# PowerBoard_p1.net
KiCad netlist of a schematic drawn in Altium Designer
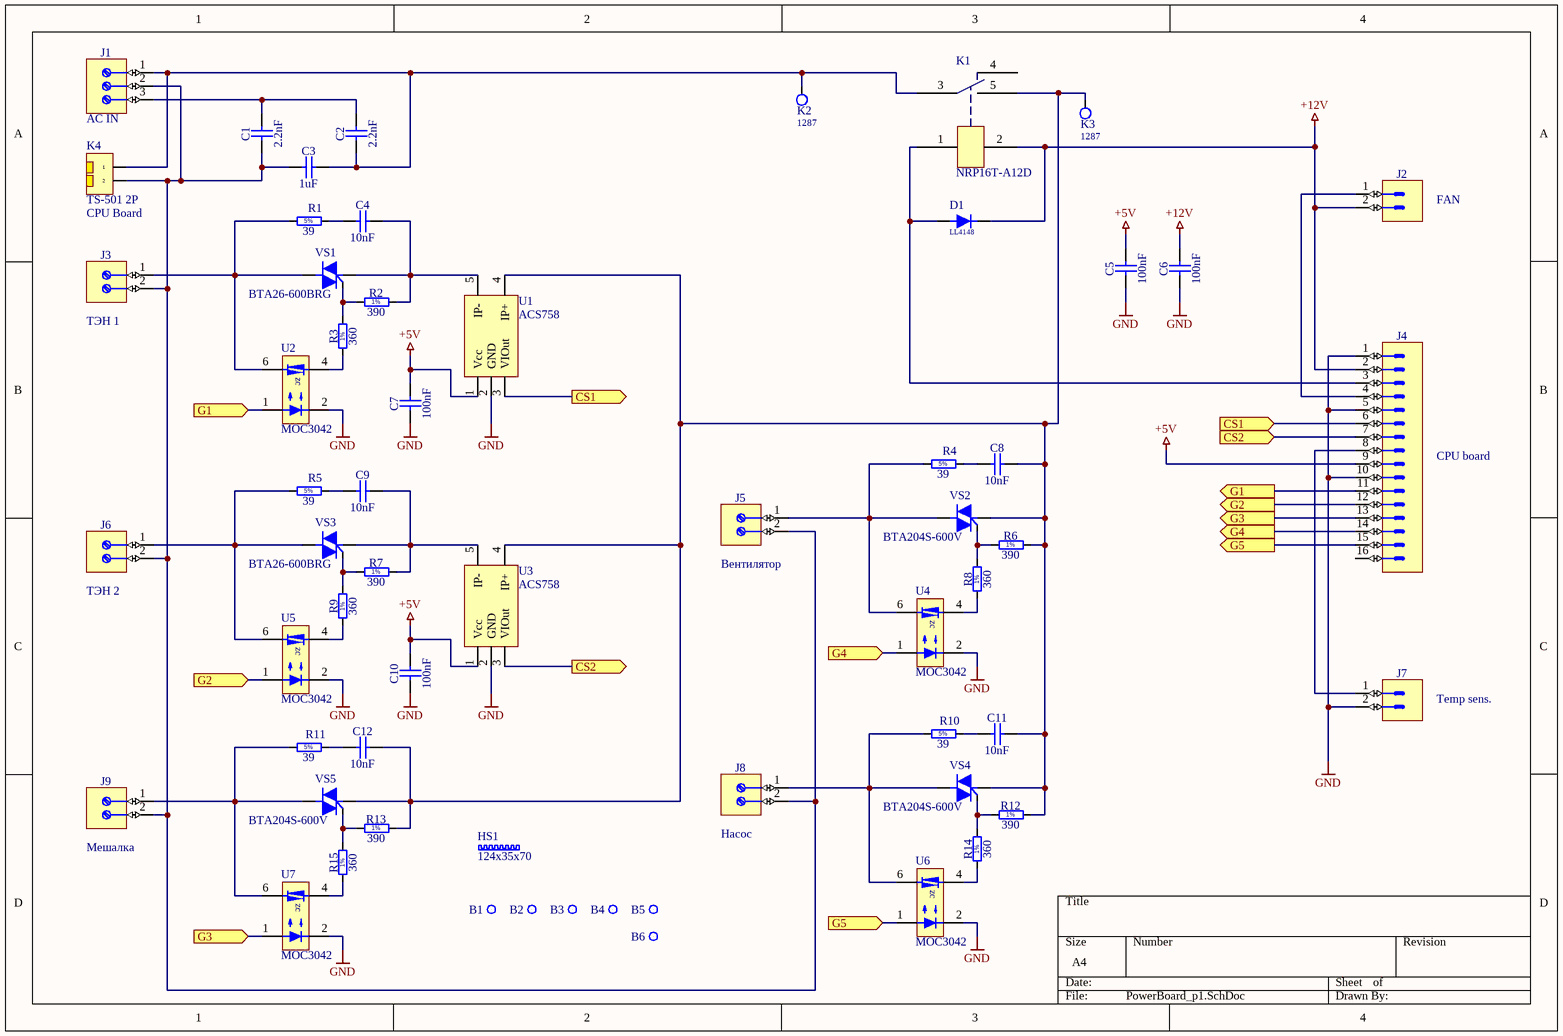
[diagram p0: PowerBoard_p1.SchDoc]

(export (version "E")
  (design (tool "Eeschema 10.0.6"))
  (components
    (comp (ref "B1")
      (value "Plated Hole")
      (footprint "MTG350_650")
      (description "Single Terminal Socket")
      (fields (field (name "PART NUMBER") "PLATED_HOLE3.5_PAD6.5") (field (name "AUTHOR") "CERN DEM JLC"))
      (libsource (lib "Eletro-mechanical") (part "Single Terminal Socket"))
    )
    (comp (ref "B2")
      (value "Plated Hole")
      (footprint "MTG350_650")
      (description "Single Terminal Socket")
      (fields (field (name "PART NUMBER") "PLATED_HOLE3.5_PAD6.5") (field (name "AUTHOR") "CERN DEM JLC"))
      (libsource (lib "Eletro-mechanical") (part "Single Terminal Socket"))
    )
    (comp (ref "B3")
      (value "Plated Hole")
      (footprint "MTG350_650")
      (description "Single Terminal Socket")
      (fields (field (name "PART NUMBER") "PLATED_HOLE3.5_PAD6.5") (field (name "AUTHOR") "CERN DEM JLC"))
      (libsource (lib "Eletro-mechanical") (part "Single Terminal Socket"))
    )
    (comp (ref "B4")
      (value "Plated Hole")
      (footprint "MTG350_650")
      (description "Single Terminal Socket")
      (fields (field (name "PART NUMBER") "PLATED_HOLE3.5_PAD6.5") (field (name "AUTHOR") "CERN DEM JLC"))
      (libsource (lib "Eletro-mechanical") (part "Single Terminal Socket"))
    )
    (comp (ref "B5")
      (value "Plated Hole")
      (footprint "MTG350_650")
      (description "Single Terminal Socket")
      (fields (field (name "PART NUMBER") "PLATED_HOLE3.5_PAD6.5") (field (name "AUTHOR") "CERN DEM JLC"))
      (libsource (lib "Eletro-mechanical") (part "Single Terminal Socket"))
    )
    (comp (ref "B6")
      (value "Plated Hole")
      (footprint "MTG350_650")
      (description "Single Terminal Socket")
      (fields (field (name "PART NUMBER") "PLATED_HOLE3.5_PAD6.5") (field (name "AUTHOR") "CERN DEM JLC"))
      (libsource (lib "Eletro-mechanical") (part "Single Terminal Socket"))
    )
    (comp (ref "C1")
      (value "2.2nF")
      (footprint "CAPRB_MURATA_DHRE4AD222Z4QB")
      (description "Non-polarised capacitor")
      (fields
        (field (name "PART NUMBER") "CCR_2.2NF_7.5KV_+80%-20%_MURATA_DHRE4AD222Z4QB")
        (field (name "VOLTAGE") "7.5kV")
        (field (name "AUTHOR") "CERN DEM JLC")
      )
      (libsource (lib "Capacitors") (part "Capacitor - non polarized"))
    )
    (comp (ref "C2")
      (value "2.2nF")
      (footprint "CAPRB_MURATA_DHRE4AD222Z4QB")
      (description "Non-polarised capacitor")
      (fields
        (field (name "PART NUMBER") "CCR_2.2NF_7.5KV_+80%-20%_MURATA_DHRE4AD222Z4QB")
        (field (name "VOLTAGE") "7.5kV")
        (field (name "AUTHOR") "CERN DEM JLC")
      )
      (libsource (lib "Capacitors") (part "Capacitor - non polarized"))
    )
    (comp (ref "C3")
      (value "1uF")
      (footprint "CAPR2750-1300X3150X2400")
      (description "Non-polarised capacitor")
      (fields
        (field (name "PART NUMBER") "CPPR_1UF_275VAC_20%_2750-1300X3150X2400")
        (field (name "VOLTAGE") "275VAC")
        (field (name "AUTHOR") "CERN DEM JLC")
      )
      (libsource (lib "Capacitors") (part "Capacitor - non polarized"))
    )
    (comp (ref "C4")
      (value "10nF")
      (footprint "CAPR500-300X720X650")
      (description "Non-polarised capacitor")
      (fields
        (field (name "PART NUMBER") "CPER_10NF_400V_10%_500-300X720X650")
        (field (name "VOLTAGE") "400VDC/200VAC")
        (field (name "AUTHOR") "CERN DEM JLC")
      )
      (libsource (lib "Capacitors") (part "Capacitor - non polarized"))
    )
    (comp (ref "C5")
      (value "100nF")
      (footprint "CAPC2012X135N")
      (description "Non-polarised capacitor")
      (fields
        (field (name "PART NUMBER") "CC0805_100NF_50V_10%_X7R")
        (field (name "VOLTAGE") "50V")
        (field (name "AUTHOR") "CERN DEM JLC")
      )
      (libsource (lib "Capacitors") (part "Capacitor - non polarized"))
    )
    (comp (ref "C6")
      (value "100nF")
      (footprint "CAPC2012X135N")
      (description "Non-polarised capacitor")
      (fields
        (field (name "PART NUMBER") "CC0805_100NF_50V_10%_X7R")
        (field (name "VOLTAGE") "50V")
        (field (name "AUTHOR") "CERN DEM JLC")
      )
      (libsource (lib "Capacitors") (part "Capacitor - non polarized"))
    )
    (comp (ref "C7")
      (value "100nF")
      (footprint "CAPC2012X135N")
      (description "Non-polarised capacitor")
      (fields
        (field (name "PART NUMBER") "CC0805_100NF_50V_10%_X7R")
        (field (name "VOLTAGE") "50V")
        (field (name "AUTHOR") "CERN DEM JLC")
      )
      (libsource (lib "Capacitors") (part "Capacitor - non polarized"))
    )
    (comp (ref "C8")
      (value "10nF")
      (footprint "CAPR500-300X720X650")
      (description "Non-polarised capacitor")
      (fields
        (field (name "PART NUMBER") "CPER_10NF_400V_10%_500-300X720X650")
        (field (name "VOLTAGE") "400VDC/200VAC")
        (field (name "AUTHOR") "CERN DEM JLC")
      )
      (libsource (lib "Capacitors") (part "Capacitor - non polarized"))
    )
    (comp (ref "C9")
      (value "10nF")
      (footprint "CAPR500-300X720X650")
      (description "Non-polarised capacitor")
      (fields
        (field (name "PART NUMBER") "CPER_10NF_400V_10%_500-300X720X650")
        (field (name "VOLTAGE") "400VDC/200VAC")
        (field (name "AUTHOR") "CERN DEM JLC")
      )
      (libsource (lib "Capacitors") (part "Capacitor - non polarized"))
    )
    (comp (ref "C10")
      (value "100nF")
      (footprint "CAPC2012X135N")
      (description "Non-polarised capacitor")
      (fields
        (field (name "PART NUMBER") "CC0805_100NF_50V_10%_X7R")
        (field (name "VOLTAGE") "50V")
        (field (name "AUTHOR") "CERN DEM JLC")
      )
      (libsource (lib "Capacitors") (part "Capacitor - non polarized"))
    )
    (comp (ref "C11")
      (value "10nF")
      (footprint "CAPR500-300X720X650")
      (description "Non-polarised capacitor")
      (fields
        (field (name "PART NUMBER") "CPER_10NF_400V_10%_500-300X720X650")
        (field (name "VOLTAGE") "400VDC/200VAC")
        (field (name "AUTHOR") "CERN DEM JLC")
      )
      (libsource (lib "Capacitors") (part "Capacitor - non polarized"))
    )
    (comp (ref "C12")
      (value "10nF")
      (footprint "CAPR500-300X720X650")
      (description "Non-polarised capacitor")
      (fields
        (field (name "PART NUMBER") "CPER_10NF_400V_10%_500-300X720X650")
        (field (name "VOLTAGE") "400VDC/200VAC")
        (field (name "AUTHOR") "CERN DEM JLC")
      )
      (libsource (lib "Capacitors") (part "Capacitor - non polarized"))
    )
    (comp (ref "D1")
      (value "LL4148")
      (footprint "SOD80/MLL34")
      (description "75V 0.3A SOD80/MLL34")
      (libsource (lib "Diodes") (part "LL4148"))
    )
    (comp (ref "HS1")
      (value "124x35x70")
      (footprint "HeadSink 124x35x70")
      (description "INDEL A5724/7")
      (libsource (lib "PowerLib") (part "HeadSink 124x35x70"))
    )
    (comp (ref "J1")
      (value "~")
      (footprint "PHOENIX_1714968")
      (description "Terminal Block, 3 Positions, Screw Connection")
      (fields
        (field (name "PART NUMBER") "PHOENIX_1714968")
        (field (name "MANUFACTURER") "PHOENIX CONTACT")
        (field (name "AUTHOR") "CERN DEM JLC")
      )
      (libsource (lib "Connectors") (part "Terminal Block_3 Positions_Screw Connection"))
    )
    (comp (ref "J2")
      (value "KK®")
      (footprint "MOLEX_22-27-2021")
      (description "Connector 2 Male")
      (fields
        (field (name "PART NUMBER") "MOLEX_22-27-2021")
        (field (name "MANUFACTURER") "MOLEX")
        (field (name "AUTHOR") "CERN DEM JLC")
      )
      (libsource (lib "Connectors") (part "Connector 2 Male"))
    )
    (comp (ref "J3")
      (value "~")
      (footprint "PHOENIX_1715721")
      (description "Terminal Block, 2 Positions, Screw Connection")
      (fields
        (field (name "PART NUMBER") "PHOENIX_1715721")
        (field (name "MANUFACTURER") "PHOENIX CONTACT")
        (field (name "AUTHOR") "CERN DEM JLC")
      )
      (libsource (lib "Connectors") (part "Terminal Block_2 Positions_Screw Connection"))
    )
    (comp (ref "J4")
      (value "Header 16")
      (footprint "3M_N2516-6002RB")
      (description "Connector 16 Male")
      (fields
        (field (name "PART NUMBER") "3M_N2516-6002RB")
        (field (name "MANUFACTURER") "3M")
        (field (name "AUTHOR") "CERN DEM JLC")
      )
      (libsource (lib "Connectors") (part "Connector 16 Male"))
    )
    (comp (ref "J5")
      (value "~")
      (footprint "PHOENIX_1715721")
      (description "Terminal Block, 2 Positions, Screw Connection")
      (fields
        (field (name "PART NUMBER") "PHOENIX_1715721")
        (field (name "MANUFACTURER") "PHOENIX CONTACT")
        (field (name "AUTHOR") "CERN DEM JLC")
      )
      (libsource (lib "Connectors") (part "Terminal Block_2 Positions_Screw Connection"))
    )
    (comp (ref "J6")
      (value "~")
      (footprint "PHOENIX_1715721")
      (description "Terminal Block, 2 Positions, Screw Connection")
      (fields
        (field (name "PART NUMBER") "PHOENIX_1715721")
        (field (name "MANUFACTURER") "PHOENIX CONTACT")
        (field (name "AUTHOR") "CERN DEM JLC")
      )
      (libsource (lib "Connectors") (part "Terminal Block_2 Positions_Screw Connection"))
    )
    (comp (ref "J7")
      (value "KK®")
      (footprint "MOLEX_22-27-2021")
      (description "Connector 2 Male")
      (fields
        (field (name "PART NUMBER") "MOLEX_22-27-2021")
        (field (name "MANUFACTURER") "MOLEX")
        (field (name "AUTHOR") "CERN DEM JLC")
      )
      (libsource (lib "Connectors") (part "Connector 2 Male"))
    )
    (comp (ref "J8")
      (value "~")
      (footprint "PHOENIX_1715721")
      (description "Terminal Block, 2 Positions, Screw Connection")
      (fields
        (field (name "PART NUMBER") "PHOENIX_1715721")
        (field (name "MANUFACTURER") "PHOENIX CONTACT")
        (field (name "AUTHOR") "CERN DEM JLC")
      )
      (libsource (lib "Connectors") (part "Terminal Block_2 Positions_Screw Connection"))
    )
    (comp (ref "J9")
      (value "~")
      (footprint "PHOENIX_1715721")
      (description "Terminal Block, 2 Positions, Screw Connection")
      (fields
        (field (name "PART NUMBER") "PHOENIX_1715721")
        (field (name "MANUFACTURER") "PHOENIX CONTACT")
        (field (name "AUTHOR") "CERN DEM JLC")
      )
      (libsource (lib "Connectors") (part "Terminal Block_2 Positions_Screw Connection"))
    )
    (comp (ref "K1")
      (value "NRP16T-A12D")
      (footprint "NRP16T")
      (libsource (lib "PowerLib") (part "Relay NRP16T-A12D"))
    )
    (comp (ref "K2")
      (value "1287")
      (footprint "Keystone 1287")
      (libsource (lib "Connektor") (part "Keystone 1287"))
    )
    (comp (ref "K3")
      (value "1287")
      (footprint "Keystone 1287")
      (libsource (lib "Connektor") (part "Keystone 1287"))
    )
    (comp (ref "K4")
      (value "TS-501 2P")
      (footprint "TS-501 2P-2.5")
      (description "10A/300V AC 5mm")
      (libsource (lib "Connektor") (part "TS-501 2P"))
    )
    (comp (ref "R1")
      (value "39")
      (footprint "RESADV508-1670X520")
      (description "Resistor - 5%")
      (fields
        (field (name "PART NUMBER") "RMF_39R_5%_3W_250PPM_508-1670X520_v")
        (field (name "POWER") "3W")
        (field (name "AUTHOR") "CERN DEM JLC")
      )
      (libsource (lib "Resistors") (part "Resistor - 5%"))
    )
    (comp (ref "R2")
      (value "390")
      (footprint "RES1016-630X250")
      (description "Resistor - 1%")
      (fields
        (field (name "PART NUMBER") "RMF_390R_1%_0.6W_50PPM_1016-630X250")
        (field (name "POWER") "0.6W")
        (field (name "AUTHOR") "CERN DEM JLC")
      )
      (libsource (lib "Resistors") (part "Resistor - 1%"))
    )
    (comp (ref "R3")
      (value "360")
      (footprint "RES1016-630X250")
      (description "Resistor - 1%")
      (fields
        (field (name "PART NUMBER") "RMF_360R_1%_0.6W_50PPM_1016-630X250")
        (field (name "POWER") "0.6W")
        (field (name "AUTHOR") "CERN DEM JLC")
      )
      (libsource (lib "Resistors") (part "Resistor - 1%"))
    )
    (comp (ref "R4")
      (value "39")
      (footprint "RESADV508-1670X520")
      (description "Resistor - 5%")
      (fields
        (field (name "PART NUMBER") "RMF_39R_5%_3W_250PPM_508-1670X520_v")
        (field (name "POWER") "3W")
        (field (name "AUTHOR") "CERN DEM JLC")
      )
      (libsource (lib "Resistors") (part "Resistor - 5%"))
    )
    (comp (ref "R5")
      (value "39")
      (footprint "RESADV508-1670X520")
      (description "Resistor - 5%")
      (fields
        (field (name "PART NUMBER") "RMF_39R_5%_3W_250PPM_508-1670X520_v")
        (field (name "POWER") "3W")
        (field (name "AUTHOR") "CERN DEM JLC")
      )
      (libsource (lib "Resistors") (part "Resistor - 5%"))
    )
    (comp (ref "R6")
      (value "390")
      (footprint "RES1016-630X250")
      (description "Resistor - 1%")
      (fields
        (field (name "PART NUMBER") "RMF_390R_1%_0.6W_50PPM_1016-630X250")
        (field (name "POWER") "0.6W")
        (field (name "AUTHOR") "CERN DEM JLC")
      )
      (libsource (lib "Resistors") (part "Resistor - 1%"))
    )
    (comp (ref "R7")
      (value "390")
      (footprint "RES1016-630X250")
      (description "Resistor - 1%")
      (fields
        (field (name "PART NUMBER") "RMF_390R_1%_0.6W_50PPM_1016-630X250")
        (field (name "POWER") "0.6W")
        (field (name "AUTHOR") "CERN DEM JLC")
      )
      (libsource (lib "Resistors") (part "Resistor - 1%"))
    )
    (comp (ref "R8")
      (value "360")
      (footprint "RES1016-630X250")
      (description "Resistor - 1%")
      (fields
        (field (name "PART NUMBER") "RMF_360R_1%_0.6W_50PPM_1016-630X250")
        (field (name "POWER") "0.6W")
        (field (name "AUTHOR") "CERN DEM JLC")
      )
      (libsource (lib "Resistors") (part "Resistor - 1%"))
    )
    (comp (ref "R9")
      (value "360")
      (footprint "RES1016-630X250")
      (description "Resistor - 1%")
      (fields
        (field (name "PART NUMBER") "RMF_360R_1%_0.6W_50PPM_1016-630X250")
        (field (name "POWER") "0.6W")
        (field (name "AUTHOR") "CERN DEM JLC")
      )
      (libsource (lib "Resistors") (part "Resistor - 1%"))
    )
    (comp (ref "R10")
      (value "39")
      (footprint "RESADV508-1670X520")
      (description "Resistor - 5%")
      (fields
        (field (name "PART NUMBER") "RMF_39R_5%_3W_250PPM_508-1670X520_v")
        (field (name "POWER") "3W")
        (field (name "AUTHOR") "CERN DEM JLC")
      )
      (libsource (lib "Resistors") (part "Resistor - 5%"))
    )
    (comp (ref "R11")
      (value "39")
      (footprint "RESADV508-1670X520")
      (description "Resistor - 5%")
      (fields
        (field (name "PART NUMBER") "RMF_39R_5%_3W_250PPM_508-1670X520_v")
        (field (name "POWER") "3W")
        (field (name "AUTHOR") "CERN DEM JLC")
      )
      (libsource (lib "Resistors") (part "Resistor - 5%"))
    )
    (comp (ref "R12")
      (value "390")
      (footprint "RES1016-630X250")
      (description "Resistor - 1%")
      (fields
        (field (name "PART NUMBER") "RMF_390R_1%_0.6W_50PPM_1016-630X250")
        (field (name "POWER") "0.6W")
        (field (name "AUTHOR") "CERN DEM JLC")
      )
      (libsource (lib "Resistors") (part "Resistor - 1%"))
    )
    (comp (ref "R13")
      (value "390")
      (footprint "RES1016-630X250")
      (description "Resistor - 1%")
      (fields
        (field (name "PART NUMBER") "RMF_390R_1%_0.6W_50PPM_1016-630X250")
        (field (name "POWER") "0.6W")
        (field (name "AUTHOR") "CERN DEM JLC")
      )
      (libsource (lib "Resistors") (part "Resistor - 1%"))
    )
    (comp (ref "R14")
      (value "360")
      (footprint "RES1016-630X250")
      (description "Resistor - 1%")
      (fields
        (field (name "PART NUMBER") "RMF_360R_1%_0.6W_50PPM_1016-630X250")
        (field (name "POWER") "0.6W")
        (field (name "AUTHOR") "CERN DEM JLC")
      )
      (libsource (lib "Resistors") (part "Resistor - 1%"))
    )
    (comp (ref "R15")
      (value "360")
      (footprint "RES1016-630X250")
      (description "Resistor - 1%")
      (fields
        (field (name "PART NUMBER") "RMF_360R_1%_0.6W_50PPM_1016-630X250")
        (field (name "POWER") "0.6W")
        (field (name "AUTHOR") "CERN DEM JLC")
      )
      (libsource (lib "Resistors") (part "Resistor - 1%"))
    )
    (comp (ref "U1") (value "ACS758") (footprint "CB Package") (libsource (lib "PowerLib") (part "ACS758")))
    (comp (ref "U2") (value "MOC3042") (footprint "DIL6-300b") (libsource (lib "PowerLib") (part "MOC3042")))
    (comp (ref "U3") (value "ACS758") (footprint "CB Package") (libsource (lib "PowerLib") (part "ACS758")))
    (comp (ref "U4") (value "MOC3042") (footprint "DIL6-300b") (libsource (lib "PowerLib") (part "MOC3042")))
    (comp (ref "U5") (value "MOC3042") (footprint "DIL6-300b") (libsource (lib "PowerLib") (part "MOC3042")))
    (comp (ref "U6") (value "MOC3042") (footprint "DIL6-300b") (libsource (lib "PowerLib") (part "MOC3042")))
    (comp (ref "U7") (value "MOC3042") (footprint "DIL6-300b") (libsource (lib "PowerLib") (part "MOC3042")))
    (comp (ref "VS1")
      (value "BTA26-600BRG")
      (footprint "TOP3-h34mm")
      (libsource (lib "PowerLib") (part "BTA26-600BRG"))
    )
    (comp (ref "VS2")
      (value "BTA204S-600V")
      (footprint "TO-252-3L (DPAK)")
      (libsource (lib "PowerLib") (part "BTA204S-600V"))
    )
    (comp (ref "VS3")
      (value "BTA26-600BRG")
      (footprint "TOP3-h34mm")
      (libsource (lib "PowerLib") (part "BTA26-600BRG"))
    )
    (comp (ref "VS4")
      (value "BTA204S-600V")
      (footprint "TO-252-3L (DPAK)")
      (libsource (lib "PowerLib") (part "BTA204S-600V"))
    )
    (comp (ref "VS5")
      (value "BTA204S-600V")
      (footprint "TO-252-3L (DPAK)")
      (libsource (lib "PowerLib") (part "BTA204S-600V"))
    )
  )
  (nets
    (net (code "1") (name "+5V") (class "Default")
      (node (ref "C10") (pin "2") (pinfunction "2_2") (pintype "passive"))
      (node (ref "C5") (pin "2") (pinfunction "2_2") (pintype "passive"))
      (node (ref "C7") (pin "2") (pinfunction "2_2") (pintype "passive"))
      (node (ref "J4") (pin "9") (pinfunction "9_9") (pintype "bidirectional"))
      (node (ref "U1") (pin "1") (pinfunction "Vcc_1") (pintype "passive"))
      (node (ref "U3") (pin "1") (pinfunction "Vcc_1") (pintype "passive"))
    )
    (net (code "2") (name "+12V") (class "Default")
      (node (ref "C6") (pin "2") (pinfunction "2_2") (pintype "passive"))
      (node (ref "D1") (pin "2") (pinfunction "C_2") (pintype "passive"))
      (node (ref "J2") (pin "2") (pinfunction "2_2") (pintype "bidirectional"))
      (node (ref "J4") (pin "2") (pinfunction "2_2") (pintype "bidirectional"))
      (node (ref "K1") (pin "2") (pinfunction "2_2") (pintype "passive"))
    )
    (net (code "3") (name "/CS1") (class "Default")
      (node (ref "J4") (pin "6") (pinfunction "6_6") (pintype "bidirectional"))
      (node (ref "U1") (pin "3") (pinfunction "VIOut_3") (pintype "passive"))
    )
    (net (code "4") (name "/CS2") (class "Default")
      (node (ref "J4") (pin "7") (pinfunction "7_7") (pintype "bidirectional"))
      (node (ref "U3") (pin "3") (pinfunction "VIOut_3") (pintype "passive"))
    )
    (net (code "5") (name "/G1") (class "Default")
      (node (ref "J4") (pin "11") (pinfunction "11_11") (pintype "bidirectional"))
      (node (ref "U2") (pin "1") (pinfunction "1_1") (pintype "passive"))
    )
    (net (code "6") (name "/G2") (class "Default")
      (node (ref "J4") (pin "12") (pinfunction "12_12") (pintype "bidirectional"))
      (node (ref "U5") (pin "1") (pinfunction "1_1") (pintype "passive"))
    )
    (net (code "7") (name "/G3") (class "Default")
      (node (ref "J4") (pin "13") (pinfunction "13_13") (pintype "bidirectional"))
      (node (ref "U7") (pin "1") (pinfunction "1_1") (pintype "passive"))
    )
    (net (code "8") (name "/G4") (class "Default")
      (node (ref "J4") (pin "14") (pinfunction "14_14") (pintype "bidirectional"))
      (node (ref "U4") (pin "1") (pinfunction "1_1") (pintype "passive"))
    )
    (net (code "9") (name "/G5") (class "Default")
      (node (ref "J4") (pin "15") (pinfunction "15_15") (pintype "bidirectional"))
      (node (ref "U6") (pin "1") (pinfunction "1_1") (pintype "passive"))
    )
    (net (code "10") (name "GND") (class "Default")
      (node (ref "C10") (pin "1") (pinfunction "1_1") (pintype "passive"))
      (node (ref "C5") (pin "1") (pinfunction "1_1") (pintype "passive"))
      (node (ref "C6") (pin "1") (pinfunction "1_1") (pintype "passive"))
      (node (ref "C7") (pin "1") (pinfunction "1_1") (pintype "passive"))
      (node (ref "J4") (pin "1") (pinfunction "1_1") (pintype "bidirectional"))
      (node (ref "J4") (pin "10") (pinfunction "10_10") (pintype "bidirectional"))
      (node (ref "J4") (pin "5") (pinfunction "5_5") (pintype "bidirectional"))
      (node (ref "J7") (pin "2") (pinfunction "2_2") (pintype "bidirectional"))
      (node (ref "U1") (pin "2") (pinfunction "GND_2") (pintype "passive"))
      (node (ref "U2") (pin "2") (pinfunction "2_2") (pintype "passive"))
      (node (ref "U3") (pin "2") (pinfunction "GND_2") (pintype "passive"))
      (node (ref "U4") (pin "2") (pinfunction "2_2") (pintype "passive"))
      (node (ref "U5") (pin "2") (pinfunction "2_2") (pintype "passive"))
      (node (ref "U6") (pin "2") (pinfunction "2_2") (pintype "passive"))
      (node (ref "U7") (pin "2") (pinfunction "2_2") (pintype "passive"))
    )
    (net (code "11") (name "Net-(C1-Pad1)") (class "Default")
      (node (ref "C1") (pin "1") (pinfunction "1_1") (pintype "passive"))
      (node (ref "C3") (pin "1") (pinfunction "1_1") (pintype "passive"))
      (node (ref "J1") (pin "2") (pinfunction "2_2") (pintype "bidirectional"))
      (node (ref "J3") (pin "2") (pinfunction "2_2") (pintype "bidirectional"))
      (node (ref "J5") (pin "2") (pinfunction "2_2") (pintype "bidirectional"))
      (node (ref "J6") (pin "2") (pinfunction "2_2") (pintype "bidirectional"))
      (node (ref "J8") (pin "2") (pinfunction "2_2") (pintype "bidirectional"))
      (node (ref "J9") (pin "2") (pinfunction "2_2") (pintype "bidirectional"))
      (node (ref "K4") (pin "2") (pinfunction "2_2") (pintype "passive"))
    )
    (net (code "12") (name "Net-(C1-Pad2)") (class "Default")
      (node (ref "C1") (pin "2") (pinfunction "2_2") (pintype "passive"))
      (node (ref "C2") (pin "2") (pinfunction "2_2") (pintype "passive"))
      (node (ref "J1") (pin "3") (pinfunction "3_3") (pintype "bidirectional"))
    )
    (net (code "13") (name "Net-(C2-Pad1)") (class "Default")
      (node (ref "C2") (pin "1") (pinfunction "1_1") (pintype "passive"))
      (node (ref "C3") (pin "2") (pinfunction "2_2") (pintype "passive"))
      (node (ref "J1") (pin "1") (pinfunction "1_1") (pintype "bidirectional"))
      (node (ref "K1") (pin "3") (pinfunction "3_3") (pintype "passive"))
      (node (ref "K2") (pin "1") (pinfunction "1_1") (pintype "passive"))
      (node (ref "K4") (pin "1") (pinfunction "1_1") (pintype "passive"))
    )
    (net (code "14") (name "Net-(C4-Pad1)") (class "Default")
      (node (ref "C4") (pin "1") (pinfunction "1_1") (pintype "passive"))
      (node (ref "R1") (pin "2") (pinfunction "2_2") (pintype "passive"))
    )
    (net (code "15") (name "Net-(C8-Pad1)") (class "Default")
      (node (ref "C8") (pin "1") (pinfunction "1_1") (pintype "passive"))
      (node (ref "R4") (pin "2") (pinfunction "2_2") (pintype "passive"))
    )
    (net (code "16") (name "Net-(C9-Pad1)") (class "Default")
      (node (ref "C9") (pin "1") (pinfunction "1_1") (pintype "passive"))
      (node (ref "R5") (pin "2") (pinfunction "2_2") (pintype "passive"))
    )
    (net (code "17") (name "Net-(C11-Pad1)") (class "Default")
      (node (ref "C11") (pin "1") (pinfunction "1_1") (pintype "passive"))
      (node (ref "R10") (pin "2") (pinfunction "2_2") (pintype "passive"))
    )
    (net (code "18") (name "Net-(C12-Pad1)") (class "Default")
      (node (ref "C12") (pin "1") (pinfunction "1_1") (pintype "passive"))
      (node (ref "R11") (pin "2") (pinfunction "2_2") (pintype "passive"))
    )
    (net (code "19") (name "Net-(D1-A)") (class "Default")
      (node (ref "D1") (pin "1") (pinfunction "A_1") (pintype "passive"))
      (node (ref "J4") (pin "3") (pinfunction "3_3") (pintype "bidirectional"))
      (node (ref "K1") (pin "1") (pinfunction "1_1") (pintype "passive"))
    )
    (net (code "20") (name "Net-(J2-Pad1)") (class "Default")
      (node (ref "J2") (pin "1") (pinfunction "1_1") (pintype "bidirectional"))
      (node (ref "J4") (pin "4") (pinfunction "4_4") (pintype "bidirectional"))
    )
    (net (code "21") (name "Net-(J4-Pad8)") (class "Default")
      (node (ref "J4") (pin "8") (pinfunction "8_8") (pintype "bidirectional"))
      (node (ref "J7") (pin "1") (pinfunction "1_1") (pintype "bidirectional"))
    )
    (net (code "22") (name "Net-(R3-Pad1)") (class "Default")
      (node (ref "R3") (pin "1") (pinfunction "1_1") (pintype "passive"))
      (node (ref "U2") (pin "4") (pinfunction "4_4") (pintype "passive"))
    )
    (net (code "23") (name "Net-(R8-Pad1)") (class "Default")
      (node (ref "R8") (pin "1") (pinfunction "1_1") (pintype "passive"))
      (node (ref "U4") (pin "4") (pinfunction "4_4") (pintype "passive"))
    )
    (net (code "24") (name "Net-(R9-Pad1)") (class "Default")
      (node (ref "R9") (pin "1") (pinfunction "1_1") (pintype "passive"))
      (node (ref "U5") (pin "4") (pinfunction "4_4") (pintype "passive"))
    )
    (net (code "25") (name "Net-(R14-Pad1)") (class "Default")
      (node (ref "R14") (pin "1") (pinfunction "1_1") (pintype "passive"))
      (node (ref "U6") (pin "4") (pinfunction "4_4") (pintype "passive"))
    )
    (net (code "26") (name "Net-(R15-Pad1)") (class "Default")
      (node (ref "R15") (pin "1") (pinfunction "1_1") (pintype "passive"))
      (node (ref "U7") (pin "4") (pinfunction "4_4") (pintype "passive"))
    )
    (net (code "27") (name "Net-(U1-IP+)") (class "Default")
      (node (ref "C11") (pin "2") (pinfunction "2_2") (pintype "passive"))
      (node (ref "C12") (pin "2") (pinfunction "2_2") (pintype "passive"))
      (node (ref "C8") (pin "2") (pinfunction "2_2") (pintype "passive"))
      (node (ref "K1") (pin "5") (pinfunction "5_5") (pintype "passive"))
      (node (ref "K3") (pin "1") (pinfunction "1_1") (pintype "passive"))
      (node (ref "R12") (pin "2") (pinfunction "2_2") (pintype "passive"))
      (node (ref "R13") (pin "2") (pinfunction "2_2") (pintype "passive"))
      (node (ref "R6") (pin "2") (pinfunction "2_2") (pintype "passive"))
      (node (ref "U1") (pin "4") (pinfunction "IP+_4") (pintype "passive"))
      (node (ref "U3") (pin "4") (pinfunction "IP+_4") (pintype "passive"))
      (node (ref "VS2") (pin "1") (pinfunction "A1_1") (pintype "passive"))
      (node (ref "VS4") (pin "1") (pinfunction "A1_1") (pintype "passive"))
      (node (ref "VS5") (pin "1") (pinfunction "A1_1") (pintype "passive"))
    )
    (net (code "28") (name "Net-(U1-IP-)") (class "Default")
      (node (ref "C4") (pin "2") (pinfunction "2_2") (pintype "passive"))
      (node (ref "R2") (pin "2") (pinfunction "2_2") (pintype "passive"))
      (node (ref "U1") (pin "5") (pinfunction "IP-_5") (pintype "passive"))
      (node (ref "VS1") (pin "1") (pinfunction "A1_1") (pintype "passive"))
    )
    (net (code "29") (name "Net-(U3-IP-)") (class "Default")
      (node (ref "C9") (pin "2") (pinfunction "2_2") (pintype "passive"))
      (node (ref "R7") (pin "2") (pinfunction "2_2") (pintype "passive"))
      (node (ref "U3") (pin "5") (pinfunction "IP-_5") (pintype "passive"))
      (node (ref "VS3") (pin "1") (pinfunction "A1_1") (pintype "passive"))
    )
    (net (code "30") (name "Net-(VS1-A2)") (class "Default")
      (node (ref "J3") (pin "1") (pinfunction "1_1") (pintype "bidirectional"))
      (node (ref "R1") (pin "1") (pinfunction "1_1") (pintype "passive"))
      (node (ref "U2") (pin "6") (pinfunction "6_6") (pintype "passive"))
      (node (ref "VS1") (pin "2") (pinfunction "A2_2") (pintype "passive"))
    )
    (net (code "31") (name "Net-(VS1-G)") (class "Default")
      (node (ref "R2") (pin "1") (pinfunction "1_1") (pintype "passive"))
      (node (ref "R3") (pin "2") (pinfunction "2_2") (pintype "passive"))
      (node (ref "VS1") (pin "3") (pinfunction "G_3") (pintype "input"))
    )
    (net (code "32") (name "Net-(VS2-A2)") (class "Default")
      (node (ref "J5") (pin "1") (pinfunction "1_1") (pintype "bidirectional"))
      (node (ref "R4") (pin "1") (pinfunction "1_1") (pintype "passive"))
      (node (ref "U4") (pin "6") (pinfunction "6_6") (pintype "passive"))
      (node (ref "VS2") (pin "2") (pinfunction "A2_2") (pintype "passive"))
    )
    (net (code "33") (name "Net-(VS2-G)") (class "Default")
      (node (ref "R6") (pin "1") (pinfunction "1_1") (pintype "passive"))
      (node (ref "R8") (pin "2") (pinfunction "2_2") (pintype "passive"))
      (node (ref "VS2") (pin "3") (pinfunction "G_3") (pintype "input"))
    )
    (net (code "34") (name "Net-(VS3-A2)") (class "Default")
      (node (ref "J6") (pin "1") (pinfunction "1_1") (pintype "bidirectional"))
      (node (ref "R5") (pin "1") (pinfunction "1_1") (pintype "passive"))
      (node (ref "U5") (pin "6") (pinfunction "6_6") (pintype "passive"))
      (node (ref "VS3") (pin "2") (pinfunction "A2_2") (pintype "passive"))
    )
    (net (code "35") (name "Net-(VS3-G)") (class "Default")
      (node (ref "R7") (pin "1") (pinfunction "1_1") (pintype "passive"))
      (node (ref "R9") (pin "2") (pinfunction "2_2") (pintype "passive"))
      (node (ref "VS3") (pin "3") (pinfunction "G_3") (pintype "input"))
    )
    (net (code "36") (name "Net-(VS4-A2)") (class "Default")
      (node (ref "J8") (pin "1") (pinfunction "1_1") (pintype "bidirectional"))
      (node (ref "R10") (pin "1") (pinfunction "1_1") (pintype "passive"))
      (node (ref "U6") (pin "6") (pinfunction "6_6") (pintype "passive"))
      (node (ref "VS4") (pin "2") (pinfunction "A2_2") (pintype "passive"))
    )
    (net (code "37") (name "Net-(VS4-G)") (class "Default")
      (node (ref "R12") (pin "1") (pinfunction "1_1") (pintype "passive"))
      (node (ref "R14") (pin "2") (pinfunction "2_2") (pintype "passive"))
      (node (ref "VS4") (pin "3") (pinfunction "G_3") (pintype "input"))
    )
    (net (code "38") (name "Net-(VS5-A2)") (class "Default")
      (node (ref "J9") (pin "1") (pinfunction "1_1") (pintype "bidirectional"))
      (node (ref "R11") (pin "1") (pinfunction "1_1") (pintype "passive"))
      (node (ref "U7") (pin "6") (pinfunction "6_6") (pintype "passive"))
      (node (ref "VS5") (pin "2") (pinfunction "A2_2") (pintype "passive"))
    )
    (net (code "39") (name "Net-(VS5-G)") (class "Default")
      (node (ref "R13") (pin "1") (pinfunction "1_1") (pintype "passive"))
      (node (ref "R15") (pin "2") (pinfunction "2_2") (pintype "passive"))
      (node (ref "VS5") (pin "3") (pinfunction "G_3") (pintype "input"))
    )
    (net (code "40") (name "unconnected-(B1-Pad1)") (class "Default")
      (node (ref "B1") (pin "1") (pinfunction "1_1") (pintype "bidirectional"))
    )
    (net (code "41") (name "unconnected-(B2-Pad1)") (class "Default")
      (node (ref "B2") (pin "1") (pinfunction "1_1") (pintype "bidirectional"))
    )
    (net (code "42") (name "unconnected-(B3-Pad1)") (class "Default")
      (node (ref "B3") (pin "1") (pinfunction "1_1") (pintype "bidirectional"))
    )
    (net (code "43") (name "unconnected-(B4-Pad1)") (class "Default")
      (node (ref "B4") (pin "1") (pinfunction "1_1") (pintype "bidirectional"))
    )
    (net (code "44") (name "unconnected-(B5-Pad1)") (class "Default")
      (node (ref "B5") (pin "1") (pinfunction "1_1") (pintype "bidirectional"))
    )
    (net (code "45") (name "unconnected-(B6-Pad1)") (class "Default")
      (node (ref "B6") (pin "1") (pinfunction "1_1") (pintype "bidirectional"))
    )
    (net (code "46") (name "unconnected-(J4-Pad16)") (class "Default")
      (node (ref "J4") (pin "16") (pinfunction "16_16") (pintype "bidirectional"))
    )
    (net (code "47") (name "unconnected-(K1-Pad4)") (class "Default")
      (node (ref "K1") (pin "4") (pinfunction "4_4") (pintype "passive"))
    )
  )
)
